# TRX_Regulator.net
KiCad netlist of a schematic drawn in Altium Designer
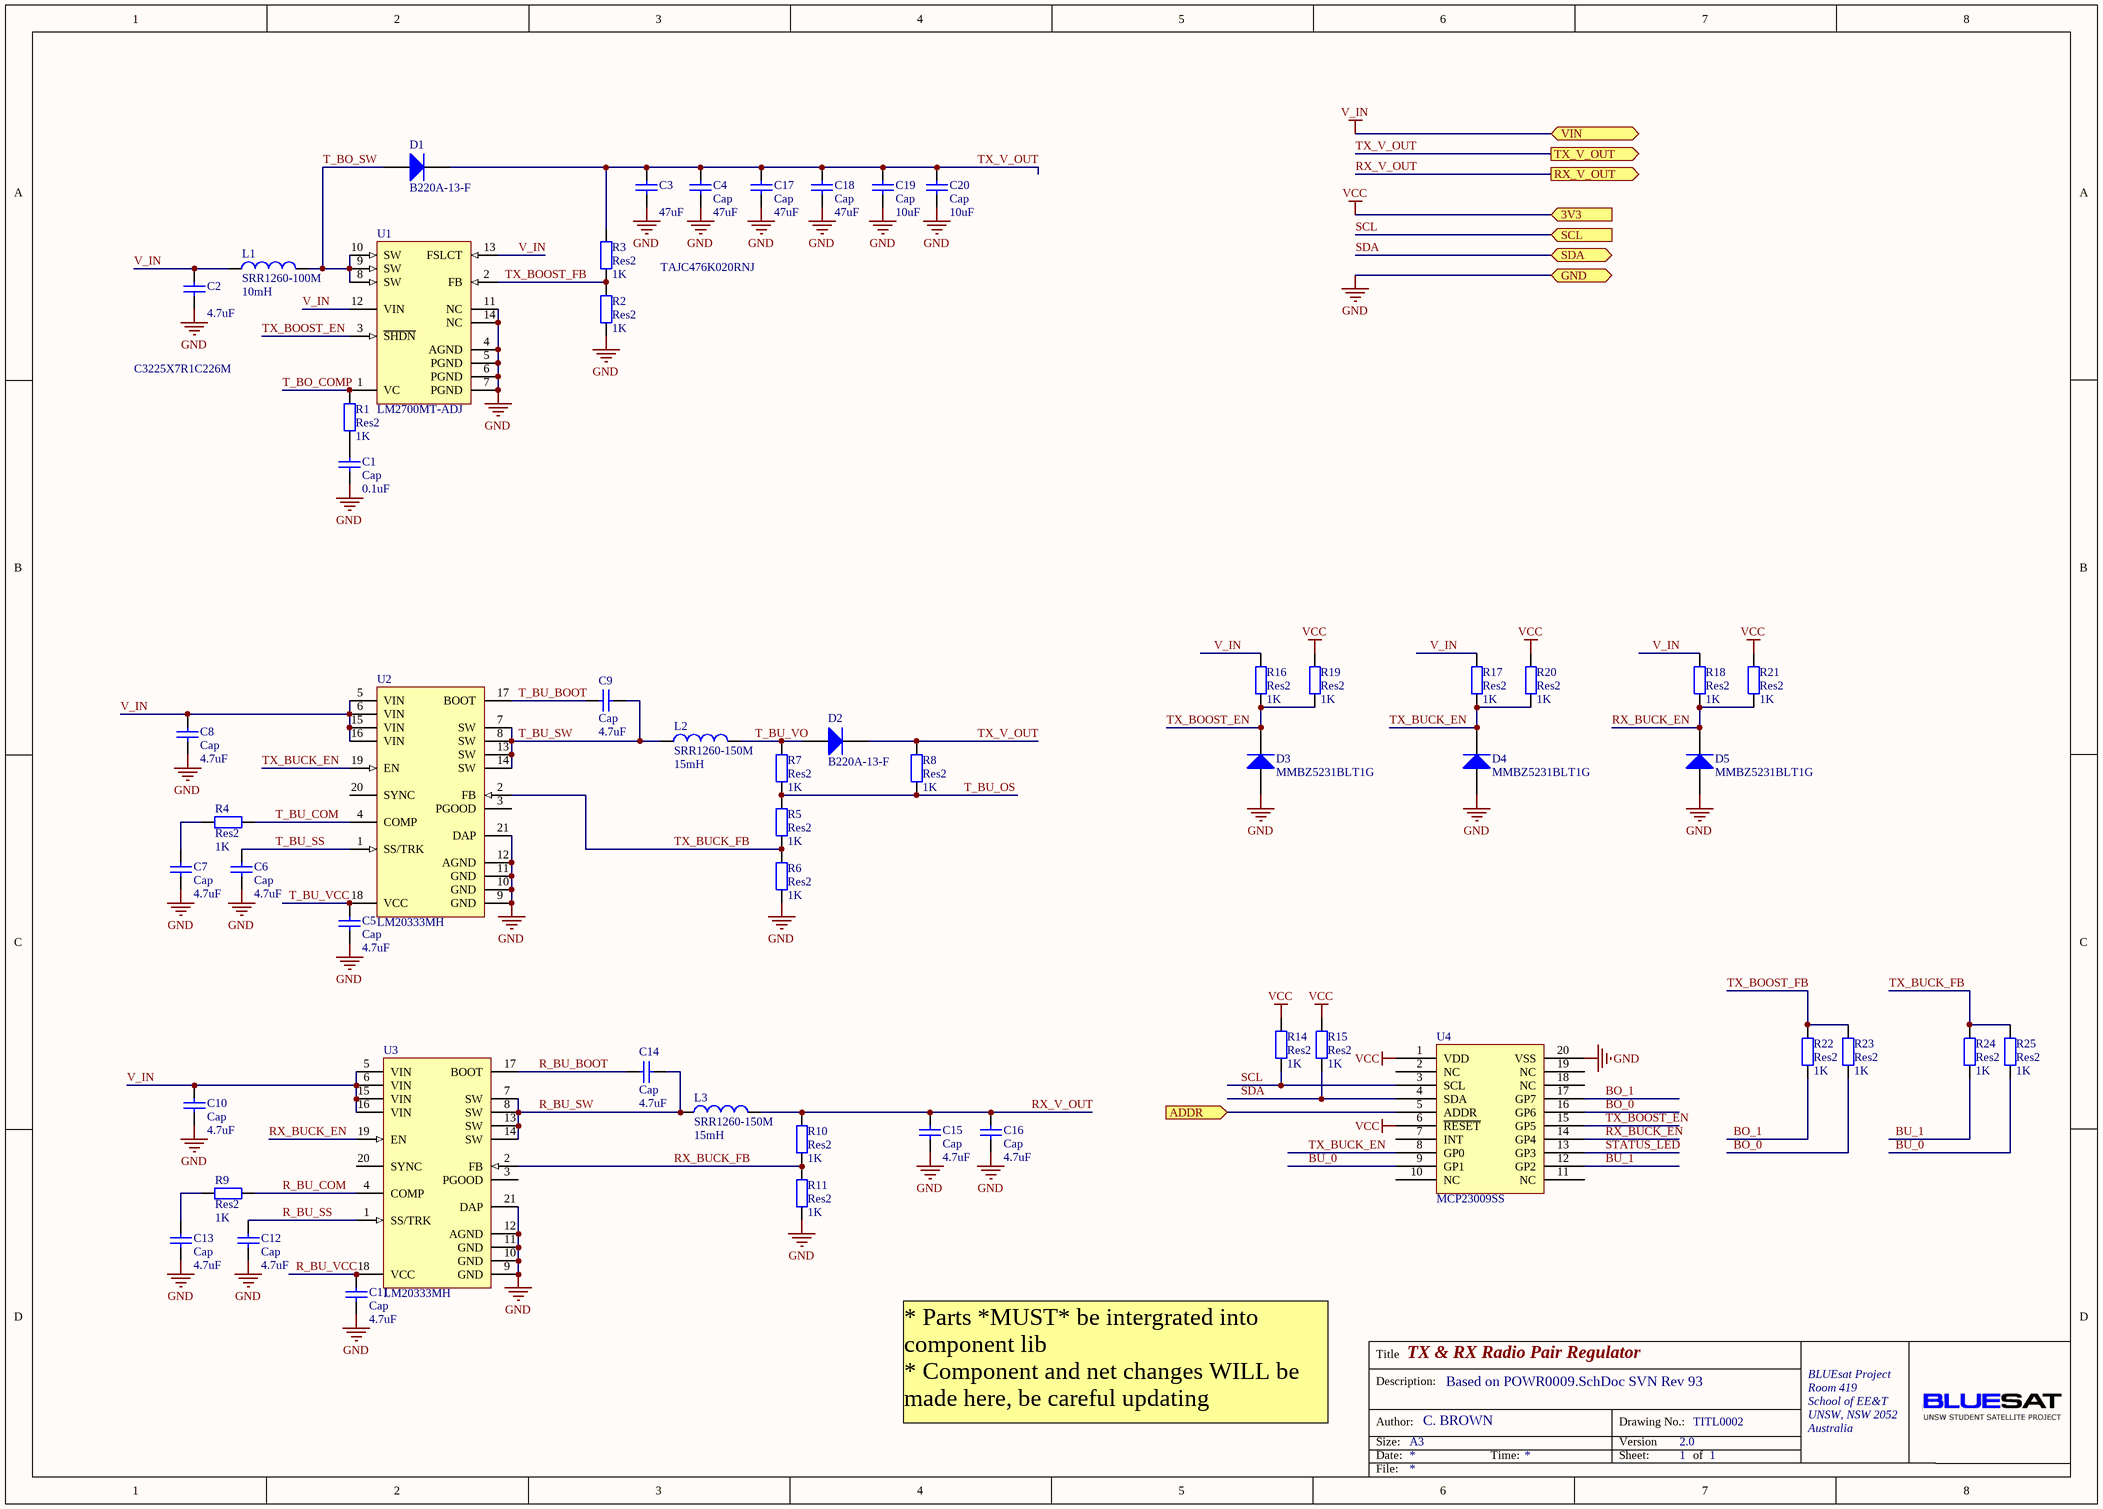
[diagram p0: TRX_Regulator.SchDoc]

(export (version "E")
  (design (tool "Eeschema 10.0.6"))
  (components
    (comp (ref "C1")
      (value "Cap")
      (footprint "R0805M")
      (description "Capacitor")
      (fields (field (name "ALTIUM_VALUE") "0.1uF") (field (name "PUBLISHER") "Altium Limited"))
      (libsource (lib "Miscellaneous Devices") (part "Cap"))
    )
    (comp (ref "C2")
      (value "C3225X7R1C226M")
      (footprint "R1210M")
      (description "Capacitor")
      (fields (field (name "ALTIUM_VALUE") "4.7uF") (field (name "PUBLISHER") "Altium Limited"))
      (libsource (lib "Miscellaneous Devices") (part "Cap"))
    )
    (comp (ref "C3")
      (value "TAJC476K020RNJ")
      (footprint "TANTCASEC")
      (description "Capacitor")
      (fields (field (name "ALTIUM_VALUE") "47uF") (field (name "PUBLISHER") "Altium Limited"))
      (libsource (lib "Miscellaneous Devices") (part "Cap"))
    )
    (comp (ref "C4")
      (value "Cap")
      (footprint "TANTCASEC")
      (description "Capacitor")
      (fields (field (name "ALTIUM_VALUE") "47uF") (field (name "PUBLISHER") "Altium Limited"))
      (libsource (lib "Miscellaneous Devices") (part "Cap"))
    )
    (comp (ref "C5")
      (value "Cap")
      (footprint "R0805M")
      (description "Capacitor")
      (fields (field (name "ALTIUM_VALUE") "4.7uF") (field (name "PUBLISHER") "Altium Limited"))
      (libsource (lib "Miscellaneous Devices") (part "Cap"))
    )
    (comp (ref "C6")
      (value "Cap")
      (footprint "R0805M")
      (description "Capacitor")
      (fields (field (name "ALTIUM_VALUE") "4.7uF") (field (name "PUBLISHER") "Altium Limited"))
      (libsource (lib "Miscellaneous Devices") (part "Cap"))
    )
    (comp (ref "C7")
      (value "Cap")
      (footprint "R0805M")
      (description "Capacitor")
      (fields (field (name "ALTIUM_VALUE") "4.7uF") (field (name "PUBLISHER") "Altium Limited"))
      (libsource (lib "Miscellaneous Devices") (part "Cap"))
    )
    (comp (ref "C8")
      (value "Cap")
      (footprint "R1210M")
      (description "Capacitor")
      (fields (field (name "ALTIUM_VALUE") "4.7uF") (field (name "PUBLISHER") "Altium Limited"))
      (libsource (lib "Miscellaneous Devices") (part "Cap"))
    )
    (comp (ref "C9")
      (value "Cap")
      (footprint "R0805M")
      (description "Capacitor")
      (fields (field (name "ALTIUM_VALUE") "4.7uF") (field (name "PUBLISHER") "Altium Limited"))
      (libsource (lib "Miscellaneous Devices") (part "Cap"))
    )
    (comp (ref "C10")
      (value "Cap")
      (footprint "R1210M")
      (description "Capacitor")
      (fields (field (name "ALTIUM_VALUE") "4.7uF") (field (name "PUBLISHER") "Altium Limited"))
      (libsource (lib "Miscellaneous Devices") (part "Cap"))
    )
    (comp (ref "C11")
      (value "Cap")
      (footprint "R0805M")
      (description "Capacitor")
      (fields (field (name "ALTIUM_VALUE") "4.7uF") (field (name "PUBLISHER") "Altium Limited"))
      (libsource (lib "Miscellaneous Devices") (part "Cap"))
    )
    (comp (ref "C12")
      (value "Cap")
      (footprint "R0805M")
      (description "Capacitor")
      (fields (field (name "ALTIUM_VALUE") "4.7uF") (field (name "PUBLISHER") "Altium Limited"))
      (libsource (lib "Miscellaneous Devices") (part "Cap"))
    )
    (comp (ref "C13")
      (value "Cap")
      (footprint "R0805M")
      (description "Capacitor")
      (fields (field (name "ALTIUM_VALUE") "4.7uF") (field (name "PUBLISHER") "Altium Limited"))
      (libsource (lib "Miscellaneous Devices") (part "Cap"))
    )
    (comp (ref "C14")
      (value "Cap")
      (footprint "R0805M")
      (description "Capacitor")
      (fields (field (name "ALTIUM_VALUE") "4.7uF") (field (name "PUBLISHER") "Altium Limited"))
      (libsource (lib "Miscellaneous Devices") (part "Cap"))
    )
    (comp (ref "C15")
      (value "Cap")
      (footprint "R0805M")
      (description "Capacitor")
      (fields (field (name "ALTIUM_VALUE") "4.7uF") (field (name "PUBLISHER") "Altium Limited"))
      (libsource (lib "Miscellaneous Devices") (part "Cap"))
    )
    (comp (ref "C16")
      (value "Cap")
      (footprint "R0805M")
      (description "Capacitor")
      (fields (field (name "ALTIUM_VALUE") "4.7uF") (field (name "PUBLISHER") "Altium Limited"))
      (libsource (lib "Miscellaneous Devices") (part "Cap"))
    )
    (comp (ref "C17")
      (value "Cap")
      (footprint "TANTCASEC")
      (description "Capacitor")
      (fields (field (name "ALTIUM_VALUE") "47uF") (field (name "PUBLISHER") "Altium Limited"))
      (libsource (lib "Miscellaneous Devices") (part "Cap"))
    )
    (comp (ref "C18")
      (value "Cap")
      (footprint "TANTCASEC")
      (description "Capacitor")
      (fields (field (name "ALTIUM_VALUE") "47uF") (field (name "PUBLISHER") "Altium Limited"))
      (libsource (lib "Miscellaneous Devices") (part "Cap"))
    )
    (comp (ref "C19")
      (value "Cap")
      (footprint "R0805M")
      (description "Capacitor")
      (fields (field (name "ALTIUM_VALUE") "10uF") (field (name "PUBLISHER") "Altium Limited"))
      (libsource (lib "Miscellaneous Devices") (part "Cap"))
    )
    (comp (ref "C20")
      (value "Cap")
      (footprint "R0805M")
      (description "Capacitor")
      (fields (field (name "ALTIUM_VALUE") "10uF") (field (name "PUBLISHER") "Altium Limited"))
      (libsource (lib "Miscellaneous Devices") (part "Cap"))
    )
    (comp (ref "D1")
      (value "B220A-13-F")
      (footprint "DIODESMA")
      (description "High Conductance Fast Diode")
      (fields (field (name "PUBLISHER") "Altium Limited"))
      (libsource (lib "Miscellaneous Devices") (part "Diode 1N4148"))
    )
    (comp (ref "D2")
      (value "B220A-13-F")
      (footprint "DIODESMA")
      (description "High Conductance Fast Diode")
      (fields (field (name "PUBLISHER") "Altium Limited"))
      (libsource (lib "Miscellaneous Devices") (part "Diode 1N4148"))
    )
    (comp (ref "D3")
      (value "MMBZ5231BLT1G")
      (footprint "SOT95P240-3N")
      (description "Silicon Switching Diode for High-Speed Switching")
      (fields (field (name "PUBLISHER") "Altium Limited"))
      (libsource (lib "Miscellaneous Devices") (part "Diode BAS16"))
    )
    (comp (ref "D4")
      (value "MMBZ5231BLT1G")
      (footprint "SOT95P240-3N")
      (description "Silicon Switching Diode for High-Speed Switching")
      (fields (field (name "PUBLISHER") "Altium Limited"))
      (libsource (lib "Miscellaneous Devices") (part "Diode BAS16"))
    )
    (comp (ref "D5")
      (value "MMBZ5231BLT1G")
      (footprint "SOT95P240-3N")
      (description "Silicon Switching Diode for High-Speed Switching")
      (fields (field (name "PUBLISHER") "Altium Limited"))
      (libsource (lib "Miscellaneous Devices") (part "Diode BAS16"))
    )
    (comp (ref "L1")
      (value "SRR1260-100M")
      (footprint "SRR1260M")
      (description "Inductor")
      (fields (field (name "ALTIUM_VALUE") "10mH") (field (name "PUBLISHER") "Altium Limited"))
      (libsource (lib "Miscellaneous Devices") (part "Inductor"))
    )
    (comp (ref "L2")
      (value "SRR1260-150M")
      (footprint "SRR1260M")
      (description "Inductor")
      (fields (field (name "ALTIUM_VALUE") "15mH") (field (name "PUBLISHER") "Altium Limited"))
      (libsource (lib "Miscellaneous Devices") (part "Inductor"))
    )
    (comp (ref "L3")
      (value "SRR1260-150M")
      (footprint "SRR1260M")
      (description "Inductor")
      (fields (field (name "ALTIUM_VALUE") "15mH") (field (name "PUBLISHER") "Altium Limited"))
      (libsource (lib "Miscellaneous Devices") (part "Inductor"))
    )
    (comp (ref "R1")
      (value "Res2")
      (footprint "R0805M")
      (description "Resistor")
      (fields (field (name "ALTIUM_VALUE") "1K") (field (name "PUBLISHER") "Altium Limited"))
      (libsource (lib "Miscellaneous Devices") (part "Res2"))
    )
    (comp (ref "R2")
      (value "Res2")
      (footprint "R0805M")
      (description "Resistor")
      (fields (field (name "ALTIUM_VALUE") "1K") (field (name "PUBLISHER") "Altium Limited"))
      (libsource (lib "Miscellaneous Devices") (part "Res2"))
    )
    (comp (ref "R3")
      (value "Res2")
      (footprint "R0805M")
      (description "Resistor")
      (fields (field (name "ALTIUM_VALUE") "1K") (field (name "PUBLISHER") "Altium Limited"))
      (libsource (lib "Miscellaneous Devices") (part "Res2"))
    )
    (comp (ref "R4")
      (value "Res2")
      (footprint "R0805M")
      (description "Resistor")
      (fields (field (name "ALTIUM_VALUE") "1K") (field (name "PUBLISHER") "Altium Limited"))
      (libsource (lib "") (part "Res2_1"))
    )
    (comp (ref "R5")
      (value "Res2")
      (footprint "R0805M")
      (description "Resistor")
      (fields (field (name "ALTIUM_VALUE") "1K") (field (name "PUBLISHER") "Altium Limited"))
      (libsource (lib "") (part "Res2_2"))
    )
    (comp (ref "R6")
      (value "Res2")
      (footprint "R0805M")
      (description "Resistor")
      (fields (field (name "ALTIUM_VALUE") "1K") (field (name "PUBLISHER") "Altium Limited"))
      (libsource (lib "") (part "Res2_2"))
    )
    (comp (ref "R7")
      (value "Res2")
      (footprint "R0805M")
      (description "Resistor")
      (fields (field (name "ALTIUM_VALUE") "1K") (field (name "PUBLISHER") "Altium Limited"))
      (libsource (lib "") (part "Res2_2"))
    )
    (comp (ref "R8")
      (value "Res2")
      (footprint "R0805M")
      (description "Resistor")
      (fields (field (name "ALTIUM_VALUE") "1K") (field (name "PUBLISHER") "Altium Limited"))
      (libsource (lib "") (part "Res2_2"))
    )
    (comp (ref "R9")
      (value "Res2")
      (footprint "R0805M")
      (description "Resistor")
      (fields (field (name "ALTIUM_VALUE") "1K") (field (name "PUBLISHER") "Altium Limited"))
      (libsource (lib "") (part "Res2_1"))
    )
    (comp (ref "R10")
      (value "Res2")
      (footprint "R0805M")
      (description "Resistor")
      (fields (field (name "ALTIUM_VALUE") "1K") (field (name "PUBLISHER") "Altium Limited"))
      (libsource (lib "Miscellaneous Devices") (part "Res2"))
    )
    (comp (ref "R11")
      (value "Res2")
      (footprint "R0805M")
      (description "Resistor")
      (fields (field (name "ALTIUM_VALUE") "1K") (field (name "PUBLISHER") "Altium Limited"))
      (libsource (lib "Miscellaneous Devices") (part "Res2"))
    )
    (comp (ref "R14")
      (value "Res2")
      (footprint "R0805M")
      (description "Resistor")
      (fields (field (name "ALTIUM_VALUE") "1K") (field (name "PUBLISHER") "Altium Limited"))
      (libsource (lib "Miscellaneous Devices") (part "Res2"))
    )
    (comp (ref "R15")
      (value "Res2")
      (footprint "R0805M")
      (description "Resistor")
      (fields (field (name "ALTIUM_VALUE") "1K") (field (name "PUBLISHER") "Altium Limited"))
      (libsource (lib "Miscellaneous Devices") (part "Res2"))
    )
    (comp (ref "R16")
      (value "Res2")
      (footprint "R0805M")
      (description "Resistor")
      (fields (field (name "ALTIUM_VALUE") "1K") (field (name "PUBLISHER") "Altium Limited"))
      (libsource (lib "Miscellaneous Devices") (part "Res2"))
    )
    (comp (ref "R17")
      (value "Res2")
      (footprint "R0805M")
      (description "Resistor")
      (fields (field (name "ALTIUM_VALUE") "1K") (field (name "PUBLISHER") "Altium Limited"))
      (libsource (lib "Miscellaneous Devices") (part "Res2"))
    )
    (comp (ref "R18")
      (value "Res2")
      (footprint "R0805M")
      (description "Resistor")
      (fields (field (name "ALTIUM_VALUE") "1K") (field (name "PUBLISHER") "Altium Limited"))
      (libsource (lib "Miscellaneous Devices") (part "Res2"))
    )
    (comp (ref "R19")
      (value "Res2")
      (footprint "R0805M")
      (description "Resistor")
      (fields (field (name "ALTIUM_VALUE") "1K") (field (name "PUBLISHER") "Altium Limited"))
      (libsource (lib "Miscellaneous Devices") (part "Res2"))
    )
    (comp (ref "R20")
      (value "Res2")
      (footprint "R0805M")
      (description "Resistor")
      (fields (field (name "ALTIUM_VALUE") "1K") (field (name "PUBLISHER") "Altium Limited"))
      (libsource (lib "Miscellaneous Devices") (part "Res2"))
    )
    (comp (ref "R21")
      (value "Res2")
      (footprint "R0805M")
      (description "Resistor")
      (fields (field (name "ALTIUM_VALUE") "1K") (field (name "PUBLISHER") "Altium Limited"))
      (libsource (lib "Miscellaneous Devices") (part "Res2"))
    )
    (comp (ref "R22")
      (value "Res2")
      (footprint "R0805M")
      (description "Resistor")
      (fields (field (name "ALTIUM_VALUE") "1K") (field (name "PUBLISHER") "Altium Limited"))
      (libsource (lib "Miscellaneous Devices") (part "Res2"))
    )
    (comp (ref "R23")
      (value "Res2")
      (footprint "R0805M")
      (description "Resistor")
      (fields (field (name "ALTIUM_VALUE") "1K") (field (name "PUBLISHER") "Altium Limited"))
      (libsource (lib "Miscellaneous Devices") (part "Res2"))
    )
    (comp (ref "R24")
      (value "Res2")
      (footprint "R0805M")
      (description "Resistor")
      (fields (field (name "ALTIUM_VALUE") "1K") (field (name "PUBLISHER") "Altium Limited"))
      (libsource (lib "Miscellaneous Devices") (part "Res2"))
    )
    (comp (ref "R25")
      (value "Res2")
      (footprint "R0805M")
      (description "Resistor")
      (fields (field (name "ALTIUM_VALUE") "1K") (field (name "PUBLISHER") "Altium Limited"))
      (libsource (lib "Miscellaneous Devices") (part "Res2"))
    )
    (comp (ref "U1")
      (value "LM2700MT-ADJ")
      (footprint "MTC14_N")
      (description "600kHz/1.25MHz, 2.5A, Step-up PWM DC/DC Converter")
      (fields
        (field (name "MANUFACTURER") "National Semiconductor")
        (field (name "DIGIKEYPARTNUMBER") "LM2700MT-ADJ-ND")
        (field (name "PUBLISHER") "Altium Limited")
      )
      (libsource (lib "NSC Switcher") (part "LM2700MT-ADJ"))
    )
    (comp (ref "U2")
      (value "LM20333MH")
      (footprint "MXA20A_N")
      (description "36V, 3A PowerWise Synchronous Buck Regulator with Frequency Synchronization")
      (fields
        (field (name "MANUFACTURER") "National Semiconductor")
        (field (name "DIGIKEYPARTNUMBER") "LM20333MH-ND")
        (field (name "PUBLISHER") "Altium Limited")
      )
      (libsource (lib "NSC Switcher") (part "LM20333MH"))
    )
    (comp (ref "U3")
      (value "LM20333MH")
      (footprint "MXA20A_N")
      (description "36V, 3A PowerWise Synchronous Buck Regulator with Frequency Synchronization")
      (fields
        (field (name "MANUFACTURER") "National Semiconductor")
        (field (name "DIGIKEYPARTNUMBER") "LM20333MH-ND")
        (field (name "PUBLISHER") "Altium Limited")
      )
      (libsource (lib "NSC Switcher") (part "LM20333MH"))
    )
    (comp (ref "U4")
      (value "MCP23009SS")
      (footprint "SSOP-SS20_M")
      (libsource (lib "VarReg") (part "MCP23009SS"))
    )
  )
  (nets
    (net (code "1") (name "/ADDR") (class "Default")
      (node (ref "U4") (pin "5") (pinfunction "ADDR_5") (pintype "passive"))
    )
    (net (code "2") (name "/BO_0") (class "Default")
      (node (ref "R23") (pin "1") (pinfunction "1_1") (pintype "passive"))
      (node (ref "U4") (pin "16") (pinfunction "GP6_16") (pintype "passive"))
    )
    (net (code "3") (name "/BO_1") (class "Default")
      (node (ref "R22") (pin "1") (pinfunction "1_1") (pintype "passive"))
      (node (ref "U4") (pin "17") (pinfunction "GP7_17") (pintype "passive"))
    )
    (net (code "4") (name "/BU_0") (class "Default")
      (node (ref "R25") (pin "1") (pinfunction "1_1") (pintype "passive"))
      (node (ref "U4") (pin "9") (pinfunction "GP1_9") (pintype "passive"))
    )
    (net (code "5") (name "/BU_1") (class "Default")
      (node (ref "R24") (pin "1") (pinfunction "1_1") (pintype "passive"))
      (node (ref "U4") (pin "12") (pinfunction "GP2_12") (pintype "passive"))
    )
    (net (code "6") (name "/RX_BUCK_EN") (class "Default")
      (node (ref "D5") (pin "3") (pinfunction "K_3") (pintype "passive"))
      (node (ref "R18") (pin "1") (pinfunction "1_1") (pintype "passive"))
      (node (ref "R21") (pin "1") (pinfunction "1_1") (pintype "passive"))
      (node (ref "U3") (pin "19") (pinfunction "EN_19") (pintype "input"))
      (node (ref "U4") (pin "14") (pinfunction "GP4_14") (pintype "passive"))
    )
    (net (code "7") (name "/RX_BUCK_FB") (class "Default")
      (node (ref "R10") (pin "1") (pinfunction "1_1") (pintype "passive"))
      (node (ref "R11") (pin "2") (pinfunction "2_2") (pintype "passive"))
      (node (ref "U3") (pin "2") (pinfunction "FB_2") (pintype "input"))
    )
    (net (code "8") (name "/RX_V_OUT") (class "Default")
      (node (ref "C15") (pin "2") (pinfunction "2_2") (pintype "passive"))
      (node (ref "C16") (pin "2") (pinfunction "2_2") (pintype "passive"))
      (node (ref "L3") (pin "2") (pinfunction "2_2") (pintype "passive"))
      (node (ref "R10") (pin "2") (pinfunction "2_2") (pintype "passive"))
    )
    (net (code "9") (name "/R_BU_BOOT") (class "Default")
      (node (ref "C14") (pin "1") (pinfunction "1_1") (pintype "passive"))
      (node (ref "U3") (pin "17") (pinfunction "BOOT_17") (pintype "passive"))
    )
    (net (code "10") (name "/R_BU_COM") (class "Default")
      (node (ref "R9") (pin "1") (pinfunction "1_1") (pintype "passive"))
      (node (ref "U3") (pin "4") (pinfunction "COMP_4") (pintype "passive"))
    )
    (net (code "11") (name "/R_BU_SS") (class "Default")
      (node (ref "C12") (pin "2") (pinfunction "2_2") (pintype "passive"))
      (node (ref "U3") (pin "1") (pinfunction "SS/TRK_1") (pintype "input"))
    )
    (net (code "12") (name "/R_BU_SW") (class "Default")
      (node (ref "C14") (pin "2") (pinfunction "2_2") (pintype "passive"))
      (node (ref "L3") (pin "1") (pinfunction "1_1") (pintype "passive"))
      (node (ref "U3") (pin "13") (pinfunction "SW_13") (pintype "power_in"))
      (node (ref "U3") (pin "14") (pinfunction "SW_14") (pintype "power_in"))
      (node (ref "U3") (pin "7") (pinfunction "SW_7") (pintype "power_in"))
      (node (ref "U3") (pin "8") (pinfunction "SW_8") (pintype "power_in"))
    )
    (net (code "13") (name "/R_BU_VCC") (class "Default")
      (node (ref "C11") (pin "2") (pinfunction "2_2") (pintype "passive"))
      (node (ref "U3") (pin "18") (pinfunction "VCC_18") (pintype "power_in"))
    )
    (net (code "14") (name "/SCL") (class "Default")
      (node (ref "R14") (pin "1") (pinfunction "1_1") (pintype "passive"))
      (node (ref "U4") (pin "3") (pinfunction "SCL_3") (pintype "passive"))
    )
    (net (code "15") (name "/SDA") (class "Default")
      (node (ref "R15") (pin "1") (pinfunction "1_1") (pintype "passive"))
      (node (ref "U4") (pin "4") (pinfunction "SDA_4") (pintype "passive"))
    )
    (net (code "16") (name "/STATUS_LED") (class "Default")
      (node (ref "U4") (pin "13") (pinfunction "GP3_13") (pintype "passive"))
    )
    (net (code "17") (name "/TX_BOOST_EN") (class "Default")
      (node (ref "D3") (pin "3") (pinfunction "K_3") (pintype "passive"))
      (node (ref "R16") (pin "1") (pinfunction "1_1") (pintype "passive"))
      (node (ref "R19") (pin "1") (pinfunction "1_1") (pintype "passive"))
      (node (ref "U1") (pin "3") (pinfunction "~{SHDN}_3") (pintype "input"))
      (node (ref "U4") (pin "15") (pinfunction "GP5_15") (pintype "passive"))
    )
    (net (code "18") (name "/TX_BOOST_FB") (class "Default")
      (node (ref "R2") (pin "2") (pinfunction "2_2") (pintype "passive"))
      (node (ref "R22") (pin "2") (pinfunction "2_2") (pintype "passive"))
      (node (ref "R23") (pin "2") (pinfunction "2_2") (pintype "passive"))
      (node (ref "R3") (pin "1") (pinfunction "1_1") (pintype "passive"))
      (node (ref "U1") (pin "2") (pinfunction "FB_2") (pintype "input"))
    )
    (net (code "19") (name "/TX_BUCK_EN") (class "Default")
      (node (ref "D4") (pin "3") (pinfunction "K_3") (pintype "passive"))
      (node (ref "R17") (pin "1") (pinfunction "1_1") (pintype "passive"))
      (node (ref "R20") (pin "1") (pinfunction "1_1") (pintype "passive"))
      (node (ref "U2") (pin "19") (pinfunction "EN_19") (pintype "input"))
      (node (ref "U4") (pin "8") (pinfunction "GP0_8") (pintype "passive"))
    )
    (net (code "20") (name "/TX_BUCK_FB") (class "Default")
      (node (ref "R24") (pin "2") (pinfunction "2_2") (pintype "passive"))
      (node (ref "R25") (pin "2") (pinfunction "2_2") (pintype "passive"))
      (node (ref "R5") (pin "2") (pinfunction "2_2") (pintype "passive"))
      (node (ref "R6") (pin "1") (pinfunction "1_1") (pintype "passive"))
      (node (ref "U2") (pin "2") (pinfunction "FB_2") (pintype "input"))
    )
    (net (code "21") (name "/TX_V_OUT") (class "Default")
      (node (ref "C17") (pin "2") (pinfunction "2_2") (pintype "passive"))
      (node (ref "C18") (pin "2") (pinfunction "2_2") (pintype "passive"))
      (node (ref "C19") (pin "2") (pinfunction "2_2") (pintype "passive"))
      (node (ref "C20") (pin "2") (pinfunction "2_2") (pintype "passive"))
      (node (ref "C3") (pin "2") (pinfunction "2_2") (pintype "passive"))
      (node (ref "C4") (pin "2") (pinfunction "2_2") (pintype "passive"))
      (node (ref "D1") (pin "2") (pinfunction "K_2") (pintype "passive"))
      (node (ref "D2") (pin "2") (pinfunction "K_2") (pintype "passive"))
      (node (ref "R3") (pin "2") (pinfunction "2_2") (pintype "passive"))
      (node (ref "R8") (pin "1") (pinfunction "1_1") (pintype "passive"))
    )
    (net (code "22") (name "/T_BO_COMP") (class "Default")
      (node (ref "R1") (pin "2") (pinfunction "2_2") (pintype "passive"))
      (node (ref "U1") (pin "1") (pinfunction "VC_1") (pintype "power_in"))
    )
    (net (code "23") (name "/T_BO_SW") (class "Default")
      (node (ref "D1") (pin "1") (pinfunction "A_1") (pintype "passive"))
      (node (ref "L1") (pin "2") (pinfunction "2_2") (pintype "passive"))
      (node (ref "U1") (pin "10") (pinfunction "SW_10") (pintype "input"))
      (node (ref "U1") (pin "8") (pinfunction "SW_8") (pintype "input"))
      (node (ref "U1") (pin "9") (pinfunction "SW_9") (pintype "input"))
    )
    (net (code "24") (name "/T_BU_BOOT") (class "Default")
      (node (ref "C9") (pin "2") (pinfunction "2_2") (pintype "passive"))
      (node (ref "U2") (pin "17") (pinfunction "BOOT_17") (pintype "passive"))
    )
    (net (code "25") (name "/T_BU_COM") (class "Default")
      (node (ref "R4") (pin "1") (pinfunction "1_1") (pintype "passive"))
      (node (ref "U2") (pin "4") (pinfunction "COMP_4") (pintype "passive"))
    )
    (net (code "26") (name "/T_BU_OS") (class "Default")
      (node (ref "R5") (pin "1") (pinfunction "1_1") (pintype "passive"))
      (node (ref "R7") (pin "2") (pinfunction "2_2") (pintype "passive"))
      (node (ref "R8") (pin "2") (pinfunction "2_2") (pintype "passive"))
    )
    (net (code "27") (name "/T_BU_SS") (class "Default")
      (node (ref "C6") (pin "2") (pinfunction "2_2") (pintype "passive"))
      (node (ref "U2") (pin "1") (pinfunction "SS/TRK_1") (pintype "input"))
    )
    (net (code "28") (name "/T_BU_SW") (class "Default")
      (node (ref "C9") (pin "1") (pinfunction "1_1") (pintype "passive"))
      (node (ref "L2") (pin "1") (pinfunction "1_1") (pintype "passive"))
      (node (ref "U2") (pin "13") (pinfunction "SW_13") (pintype "power_in"))
      (node (ref "U2") (pin "14") (pinfunction "SW_14") (pintype "power_in"))
      (node (ref "U2") (pin "7") (pinfunction "SW_7") (pintype "power_in"))
      (node (ref "U2") (pin "8") (pinfunction "SW_8") (pintype "power_in"))
    )
    (net (code "29") (name "/T_BU_VCC") (class "Default")
      (node (ref "C5") (pin "2") (pinfunction "2_2") (pintype "passive"))
      (node (ref "U2") (pin "18") (pinfunction "VCC_18") (pintype "power_in"))
    )
    (net (code "30") (name "/T_BU_VO") (class "Default")
      (node (ref "D2") (pin "1") (pinfunction "A_1") (pintype "passive"))
      (node (ref "L2") (pin "2") (pinfunction "2_2") (pintype "passive"))
      (node (ref "R7") (pin "1") (pinfunction "1_1") (pintype "passive"))
    )
    (net (code "31") (name "GND") (class "Default")
      (node (ref "C1") (pin "1") (pinfunction "1_1") (pintype "passive"))
      (node (ref "C10") (pin "1") (pinfunction "1_1") (pintype "passive"))
      (node (ref "C11") (pin "1") (pinfunction "1_1") (pintype "passive"))
      (node (ref "C12") (pin "1") (pinfunction "1_1") (pintype "passive"))
      (node (ref "C13") (pin "1") (pinfunction "1_1") (pintype "passive"))
      (node (ref "C15") (pin "1") (pinfunction "1_1") (pintype "passive"))
      (node (ref "C16") (pin "1") (pinfunction "1_1") (pintype "passive"))
      (node (ref "C17") (pin "1") (pinfunction "1_1") (pintype "passive"))
      (node (ref "C18") (pin "1") (pinfunction "1_1") (pintype "passive"))
      (node (ref "C19") (pin "1") (pinfunction "1_1") (pintype "passive"))
      (node (ref "C2") (pin "1") (pinfunction "1_1") (pintype "passive"))
      (node (ref "C20") (pin "1") (pinfunction "1_1") (pintype "passive"))
      (node (ref "C3") (pin "1") (pinfunction "1_1") (pintype "passive"))
      (node (ref "C4") (pin "1") (pinfunction "1_1") (pintype "passive"))
      (node (ref "C5") (pin "1") (pinfunction "1_1") (pintype "passive"))
      (node (ref "C6") (pin "1") (pinfunction "1_1") (pintype "passive"))
      (node (ref "C7") (pin "1") (pinfunction "1_1") (pintype "passive"))
      (node (ref "C8") (pin "1") (pinfunction "1_1") (pintype "passive"))
      (node (ref "D3") (pin "1") (pinfunction "A_1") (pintype "passive"))
      (node (ref "D4") (pin "1") (pinfunction "A_1") (pintype "passive"))
      (node (ref "D5") (pin "1") (pinfunction "A_1") (pintype "passive"))
      (node (ref "R11") (pin "1") (pinfunction "1_1") (pintype "passive"))
      (node (ref "R2") (pin "1") (pinfunction "1_1") (pintype "passive"))
      (node (ref "R6") (pin "2") (pinfunction "2_2") (pintype "passive"))
      (node (ref "U1") (pin "11") (pinfunction "NC_11") (pintype "passive"))
      (node (ref "U1") (pin "14") (pinfunction "NC_14") (pintype "passive"))
      (node (ref "U1") (pin "4") (pinfunction "AGND_4") (pintype "power_in"))
      (node (ref "U1") (pin "5") (pinfunction "PGND_5") (pintype "power_in"))
      (node (ref "U1") (pin "6") (pinfunction "PGND_6") (pintype "power_in"))
      (node (ref "U1") (pin "7") (pinfunction "PGND_7") (pintype "power_in"))
      (node (ref "U2") (pin "10") (pinfunction "GND_10") (pintype "power_in"))
      (node (ref "U2") (pin "11") (pinfunction "GND_11") (pintype "power_in"))
      (node (ref "U2") (pin "12") (pinfunction "AGND_12") (pintype "power_in"))
      (node (ref "U2") (pin "21") (pinfunction "DAP_21") (pintype "power_in"))
      (node (ref "U2") (pin "9") (pinfunction "GND_9") (pintype "power_in"))
      (node (ref "U3") (pin "10") (pinfunction "GND_10") (pintype "power_in"))
      (node (ref "U3") (pin "11") (pinfunction "GND_11") (pintype "power_in"))
      (node (ref "U3") (pin "12") (pinfunction "AGND_12") (pintype "power_in"))
      (node (ref "U3") (pin "21") (pinfunction "DAP_21") (pintype "power_in"))
      (node (ref "U3") (pin "9") (pinfunction "GND_9") (pintype "power_in"))
      (node (ref "U4") (pin "20") (pinfunction "VSS_20") (pintype "passive"))
    )
    (net (code "32") (name "Net-(C1-Pad2)") (class "Default")
      (node (ref "C1") (pin "2") (pinfunction "2_2") (pintype "passive"))
      (node (ref "R1") (pin "1") (pinfunction "1_1") (pintype "passive"))
    )
    (net (code "33") (name "Net-(C7-Pad2)") (class "Default")
      (node (ref "C7") (pin "2") (pinfunction "2_2") (pintype "passive"))
      (node (ref "R4") (pin "2") (pinfunction "2_2") (pintype "passive"))
    )
    (net (code "34") (name "Net-(C13-Pad2)") (class "Default")
      (node (ref "C13") (pin "2") (pinfunction "2_2") (pintype "passive"))
      (node (ref "R9") (pin "2") (pinfunction "2_2") (pintype "passive"))
    )
    (net (code "35") (name "VCC") (class "Default")
      (node (ref "R14") (pin "2") (pinfunction "2_2") (pintype "passive"))
      (node (ref "R15") (pin "2") (pinfunction "2_2") (pintype "passive"))
      (node (ref "R19") (pin "2") (pinfunction "2_2") (pintype "passive"))
      (node (ref "R20") (pin "2") (pinfunction "2_2") (pintype "passive"))
      (node (ref "R21") (pin "2") (pinfunction "2_2") (pintype "passive"))
      (node (ref "U4") (pin "1") (pinfunction "VDD_1") (pintype "passive"))
      (node (ref "U4") (pin "6") (pinfunction "~{RESET}_6") (pintype "passive"))
    )
    (net (code "36") (name "V_IN") (class "Default")
      (node (ref "C10") (pin "2") (pinfunction "2_2") (pintype "passive"))
      (node (ref "C2") (pin "2") (pinfunction "2_2") (pintype "passive"))
      (node (ref "C8") (pin "2") (pinfunction "2_2") (pintype "passive"))
      (node (ref "L1") (pin "1") (pinfunction "1_1") (pintype "passive"))
      (node (ref "R16") (pin "2") (pinfunction "2_2") (pintype "passive"))
      (node (ref "R17") (pin "2") (pinfunction "2_2") (pintype "passive"))
      (node (ref "R18") (pin "2") (pinfunction "2_2") (pintype "passive"))
      (node (ref "U1") (pin "12") (pinfunction "VIN_12") (pintype "power_in"))
      (node (ref "U1") (pin "13") (pinfunction "FSLCT_13") (pintype "input"))
      (node (ref "U2") (pin "15") (pinfunction "VIN_15") (pintype "power_in"))
      (node (ref "U2") (pin "16") (pinfunction "VIN_16") (pintype "power_in"))
      (node (ref "U2") (pin "5") (pinfunction "VIN_5") (pintype "power_in"))
      (node (ref "U2") (pin "6") (pinfunction "VIN_6") (pintype "power_in"))
      (node (ref "U3") (pin "15") (pinfunction "VIN_15") (pintype "power_in"))
      (node (ref "U3") (pin "16") (pinfunction "VIN_16") (pintype "power_in"))
      (node (ref "U3") (pin "5") (pinfunction "VIN_5") (pintype "power_in"))
      (node (ref "U3") (pin "6") (pinfunction "VIN_6") (pintype "power_in"))
    )
    (net (code "37") (name "unconnected-(U2-PGOOD-Pad3)") (class "Default")
      (node (ref "U2") (pin "3") (pinfunction "PGOOD_3") (pintype "open_collector"))
    )
    (net (code "38") (name "unconnected-(U2-SYNC-Pad20)") (class "Default")
      (node (ref "U2") (pin "20") (pinfunction "SYNC_20") (pintype "passive"))
    )
    (net (code "39") (name "unconnected-(U3-PGOOD-Pad3)") (class "Default")
      (node (ref "U3") (pin "3") (pinfunction "PGOOD_3") (pintype "open_collector"))
    )
    (net (code "40") (name "unconnected-(U3-SYNC-Pad20)") (class "Default")
      (node (ref "U3") (pin "20") (pinfunction "SYNC_20") (pintype "passive"))
    )
    (net (code "41") (name "unconnected-(U4-INT-Pad7)") (class "Default")
      (node (ref "U4") (pin "7") (pinfunction "INT_7") (pintype "passive"))
    )
    (net (code "42") (name "unconnected-(U4-NC-Pad2)") (class "Default")
      (node (ref "U4") (pin "2") (pinfunction "NC_2") (pintype "passive"))
    )
    (net (code "43") (name "unconnected-(U4-NC-Pad10)") (class "Default")
      (node (ref "U4") (pin "10") (pinfunction "NC_10") (pintype "passive"))
    )
    (net (code "44") (name "unconnected-(U4-NC-Pad11)") (class "Default")
      (node (ref "U4") (pin "11") (pinfunction "NC_11") (pintype "passive"))
    )
    (net (code "45") (name "unconnected-(U4-NC-Pad18)") (class "Default")
      (node (ref "U4") (pin "18") (pinfunction "NC_18") (pintype "passive"))
    )
    (net (code "46") (name "unconnected-(U4-NC-Pad19)") (class "Default")
      (node (ref "U4") (pin "19") (pinfunction "NC_19") (pintype "passive"))
    )
  )
)
